# PSRAM.net
KiCad netlist of a schematic drawn in Altium Designer
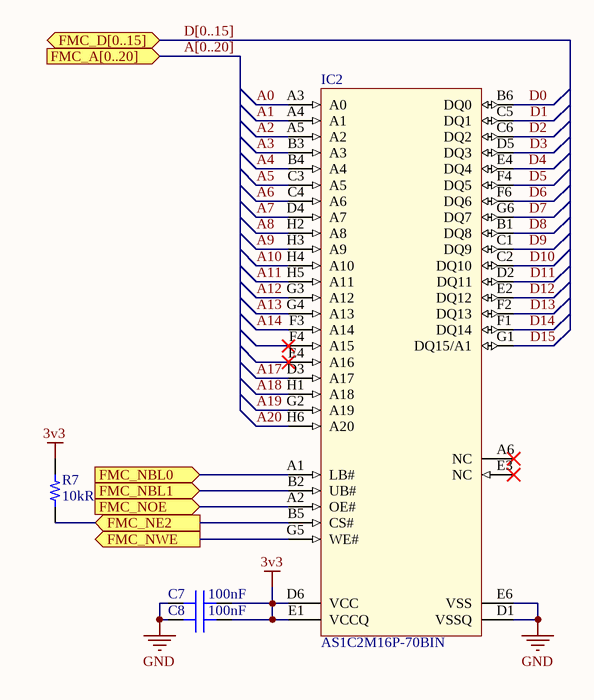
[diagram p0: PSRAM.SchDoc]

(export (version "E")
  (design (tool "Eeschema 10.0.6"))
  (components
    (comp (ref "C7")
      (value "100nF")
      (footprint "CAP 0603/1608")
      (description "Ceramic, SMT Capacitor")
      (fields
        (field (name "MANUFACTURER") "Samsung")
        (field (name "MANUFACTURER PART NUMBER") "CL10B104JB8NNNC")
      )
      (libsource (lib "yildizIoT Library") (part "Capacitor - Ceramic"))
    )
    (comp (ref "C8")
      (value "100nF")
      (footprint "CAP 0603/1608")
      (description "Ceramic, SMT Capacitor")
      (fields
        (field (name "MANUFACTURER") "Samsung")
        (field (name "MANUFACTURER PART NUMBER") "CL10B104JB8NNNC")
      )
      (libsource (lib "yildizIoT Library") (part "Capacitor - Ceramic"))
    )
    (comp (ref "IC2")
      (value "AS1C2M16P-70BIN")
      (footprint "Alliance VFBGA-48 6x7")
      (description "32-Mbit (4M x 8-bit / 2M x16 Pseudo Static RAM Specification")
      (fields (field (name "MANUFACTURER") "Alliance Memory"))
      (libsource (lib "yildizIoT Library") (part "Alliance AS1C2M16P-70BIN"))
    )
    (comp (ref "R7")
      (value "10kR")
      (footprint "RES 0603/1608")
      (description "Ceramic, SMT Capacitor")
      (fields
        (field (name "MANUFACTURER") "Stackpole Electronics")
        (field (name "MANUFACTURER PART NUMBER") "RNCP0603FTD10K0")
      )
      (libsource (lib "yildizIoT Library") (part "Resistor_Chip"))
    )
  )
  (nets
    (net (code "3") (name "/A0") (class "Default")
      (node (ref "IC2") (pin "A3") (pinfunction "A0_A3") (pintype "input"))
    )
    (net (code "4") (name "/A1") (class "Default")
      (node (ref "IC2") (pin "A4") (pinfunction "A1_A4") (pintype "input"))
    )
    (net (code "5") (name "/A2") (class "Default")
      (node (ref "IC2") (pin "A5") (pinfunction "A2_A5") (pintype "input"))
    )
    (net (code "6") (name "/A3") (class "Default")
      (node (ref "IC2") (pin "B3") (pinfunction "A3_B3") (pintype "input"))
    )
    (net (code "7") (name "/A4") (class "Default")
      (node (ref "IC2") (pin "B4") (pinfunction "A4_B4") (pintype "input"))
    )
    (net (code "8") (name "/A5") (class "Default")
      (node (ref "IC2") (pin "C3") (pinfunction "A5_C3") (pintype "input"))
    )
    (net (code "9") (name "/A6") (class "Default")
      (node (ref "IC2") (pin "C4") (pinfunction "A6_C4") (pintype "input"))
    )
    (net (code "10") (name "/A7") (class "Default")
      (node (ref "IC2") (pin "D4") (pinfunction "A7_D4") (pintype "input"))
    )
    (net (code "11") (name "/A8") (class "Default")
      (node (ref "IC2") (pin "H2") (pinfunction "A8_H2") (pintype "input"))
    )
    (net (code "12") (name "/A9") (class "Default")
      (node (ref "IC2") (pin "H3") (pinfunction "A9_H3") (pintype "input"))
    )
    (net (code "13") (name "/A10") (class "Default")
      (node (ref "IC2") (pin "H4") (pinfunction "A10_H4") (pintype "input"))
    )
    (net (code "14") (name "/A11") (class "Default")
      (node (ref "IC2") (pin "H5") (pinfunction "A11_H5") (pintype "input"))
    )
    (net (code "15") (name "/A12") (class "Default")
      (node (ref "IC2") (pin "G3") (pinfunction "A12_G3") (pintype "input"))
    )
    (net (code "16") (name "/A13") (class "Default")
      (node (ref "IC2") (pin "G4") (pinfunction "A13_G4") (pintype "input"))
    )
    (net (code "17") (name "/A14") (class "Default")
      (node (ref "IC2") (pin "F3") (pinfunction "A14_F3") (pintype "input"))
    )
    (net (code "18") (name "/A17") (class "Default")
      (node (ref "IC2") (pin "D3") (pinfunction "A17_D3") (pintype "input"))
    )
    (net (code "19") (name "/A18") (class "Default")
      (node (ref "IC2") (pin "H1") (pinfunction "A18_H1") (pintype "input"))
    )
    (net (code "20") (name "/A19") (class "Default")
      (node (ref "IC2") (pin "G2") (pinfunction "A19_G2") (pintype "input"))
    )
    (net (code "21") (name "/A20") (class "Default")
      (node (ref "IC2") (pin "H6") (pinfunction "A20_H6") (pintype "input"))
    )
    (net (code "23") (name "/D0") (class "Default")
      (node (ref "IC2") (pin "B6") (pinfunction "DQ0_B6") (pintype "bidirectional"))
    )
    (net (code "24") (name "/D1") (class "Default")
      (node (ref "IC2") (pin "C5") (pinfunction "DQ1_C5") (pintype "bidirectional"))
    )
    (net (code "25") (name "/D2") (class "Default")
      (node (ref "IC2") (pin "C6") (pinfunction "DQ2_C6") (pintype "bidirectional"))
    )
    (net (code "26") (name "/D3") (class "Default")
      (node (ref "IC2") (pin "D5") (pinfunction "DQ3_D5") (pintype "bidirectional"))
    )
    (net (code "27") (name "/D4") (class "Default")
      (node (ref "IC2") (pin "E4") (pinfunction "DQ4_E4") (pintype "bidirectional"))
    )
    (net (code "28") (name "/D5") (class "Default")
      (node (ref "IC2") (pin "F4") (pinfunction "DQ5_F4") (pintype "bidirectional"))
    )
    (net (code "29") (name "/D6") (class "Default")
      (node (ref "IC2") (pin "F6") (pinfunction "DQ6_F6") (pintype "bidirectional"))
    )
    (net (code "30") (name "/D7") (class "Default")
      (node (ref "IC2") (pin "G6") (pinfunction "DQ7_G6") (pintype "bidirectional"))
    )
    (net (code "31") (name "/D8") (class "Default")
      (node (ref "IC2") (pin "B1") (pinfunction "DQ8_B1") (pintype "bidirectional"))
    )
    (net (code "32") (name "/D9") (class "Default")
      (node (ref "IC2") (pin "C1") (pinfunction "DQ9_C1") (pintype "bidirectional"))
    )
    (net (code "33") (name "/D10") (class "Default")
      (node (ref "IC2") (pin "C2") (pinfunction "DQ10_C2") (pintype "bidirectional"))
    )
    (net (code "34") (name "/D11") (class "Default")
      (node (ref "IC2") (pin "D2") (pinfunction "DQ11_D2") (pintype "bidirectional"))
    )
    (net (code "35") (name "/D12") (class "Default")
      (node (ref "IC2") (pin "E2") (pinfunction "DQ12_E2") (pintype "bidirectional"))
    )
    (net (code "36") (name "/D13") (class "Default")
      (node (ref "IC2") (pin "F2") (pinfunction "DQ13_F2") (pintype "bidirectional"))
    )
    (net (code "37") (name "/D14") (class "Default")
      (node (ref "IC2") (pin "F1") (pinfunction "DQ14_F1") (pintype "bidirectional"))
    )
    (net (code "38") (name "/D15") (class "Default")
      (node (ref "IC2") (pin "G1") (pinfunction "DQ15/A1_G1") (pintype "bidirectional"))
    )
    (net (code "40") (name "/FMC_NBL0") (class "Default")
      (node (ref "IC2") (pin "A1") (pinfunction "LB#_A1") (pintype "input"))
    )
    (net (code "41") (name "/FMC_NBL1") (class "Default")
      (node (ref "IC2") (pin "B2") (pinfunction "UB#_B2") (pintype "input"))
    )
    (net (code "42") (name "/FMC_NE2") (class "Default")
      (node (ref "IC2") (pin "B5") (pinfunction "CS#_B5") (pintype "input"))
      (node (ref "R7") (pin "2") (pinfunction "2_2") (pintype "passive"))
    )
    (net (code "43") (name "/FMC_NOE") (class "Default")
      (node (ref "IC2") (pin "A2") (pinfunction "OE#_A2") (pintype "input"))
    )
    (net (code "44") (name "/FMC_NWE") (class "Default")
      (node (ref "IC2") (pin "G5") (pinfunction "WE#_G5") (pintype "input"))
    )
    (net (code "45") (name "3v3") (class "Default")
      (node (ref "C7") (pin "1") (pinfunction "1_1") (pintype "passive"))
      (node (ref "C8") (pin "1") (pinfunction "1_1") (pintype "passive"))
      (node (ref "IC2") (pin "D6") (pinfunction "VCC_D6") (pintype "power_in"))
      (node (ref "IC2") (pin "E1") (pinfunction "VCCQ_E1") (pintype "power_in"))
      (node (ref "R7") (pin "1") (pinfunction "1_1") (pintype "passive"))
    )
    (net (code "46") (name "GND") (class "Default")
      (node (ref "C7") (pin "2") (pinfunction "2_2") (pintype "passive"))
      (node (ref "C8") (pin "2") (pinfunction "2_2") (pintype "passive"))
      (node (ref "IC2") (pin "D1") (pinfunction "VSSQ_D1") (pintype "power_in"))
      (node (ref "IC2") (pin "E6") (pinfunction "VSS_E6") (pintype "power_in"))
    )
    (net (code "47") (name "unconnected-(IC2-A15-PadF4)") (class "Default")
      (node (ref "IC2") (pin "F4") (pinfunction "A15_F4") (pintype "input+no_connect"))
    )
    (net (code "48") (name "unconnected-(IC2-A16-PadE4)") (class "Default")
      (node (ref "IC2") (pin "E4") (pinfunction "A16_E4") (pintype "input+no_connect"))
    )
    (net (code "49") (name "unconnected-(IC2-NC-PadA6)") (class "Default")
      (node (ref "IC2") (pin "A6") (pinfunction "NC_A6") (pintype "passive+no_connect"))
    )
    (net (code "50") (name "unconnected-(IC2-NC-PadE3)") (class "Default")
      (node (ref "IC2") (pin "E3") (pinfunction "NC_E3") (pintype "input+no_connect"))
    )
  )
)
